# LipStick.net
KiCad netlist of a schematic drawn in EAGLE
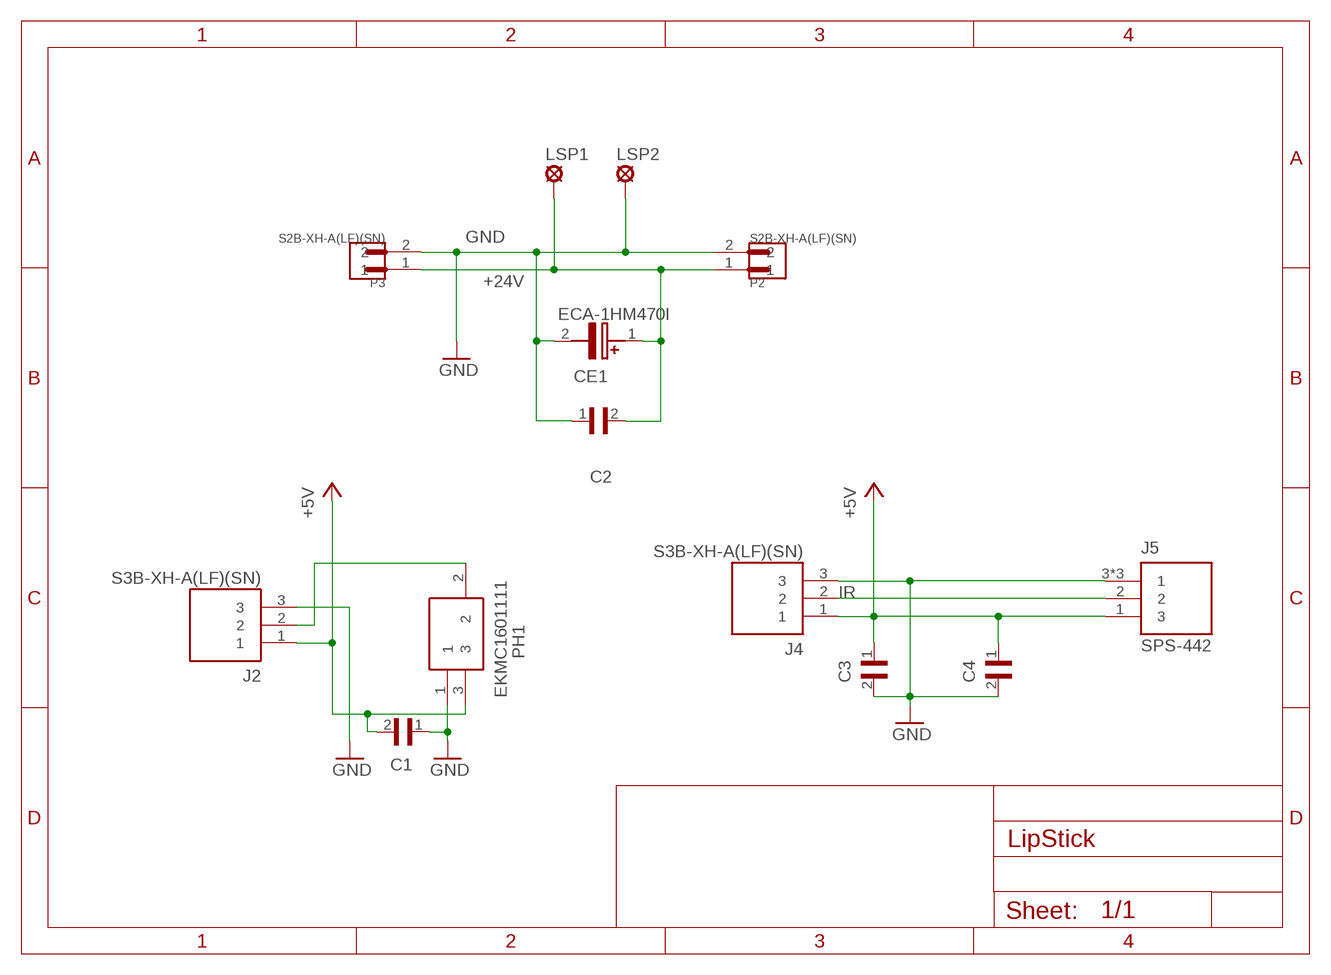
[diagram p0: schematic, sheet 1]

(export (version "E")
  (design (tool "Eeschema 10.0.6"))
  (components
    (comp (ref "C1")
      (value "GRM188R71H104KA93D")
      (footprint "eagle-import:CAPC1608X90N")
      (fields (field (name "MF") "Murata"))
      (libsource (lib "eagle-import") (part "GRM188R71H104KA93D"))
    )
    (comp (ref "C2")
      (value "GRM188R71H104KA93D")
      (footprint "eagle-import:CAPC1608X90N")
      (fields (field (name "MF") "Murata"))
      (libsource (lib "eagle-import") (part "GRM188R71H104KA93D"))
    )
    (comp (ref "C3")
      (value "GRM188R71H104KA93D")
      (footprint "eagle-import:CAPC1608X90N")
      (fields (field (name "MF") "Murata"))
      (libsource (lib "eagle-import") (part "GRM188R71H104KA93D"))
    )
    (comp (ref "C4")
      (value "GRM188R71H104KA93D")
      (footprint "eagle-import:CAPC1608X90N")
      (fields (field (name "MF") "Murata"))
      (libsource (lib "eagle-import") (part "GRM188R71H104KA93D"))
    )
    (comp (ref "CE1")
      (value "ECA-1HM470I")
      (footprint "eagle-import:CAPPRD250W55D630H1220")
      (fields (field (name "MOUSER_PART_NUMBER") "667-ECA-1HM470I"))
      (libsource (lib "eagle-import") (part "ECA-1HM470I"))
    )
    (comp (ref "J2")
      (value "S3B-XH-A(LF)(SN)")
      (footprint "eagle-import:JST_S3B-XH-A(LF)(SN)")
      (fields (field (name "DIGI-KEY_PART_NUMBER") "455-2250-ND") (field (name "MF") "JST Sales"))
      (libsource (lib "eagle-import") (part "S3B-XH-A(LF)(SN)"))
    )
    (comp (ref "J4")
      (value "S3B-XH-A(LF)(SN)")
      (footprint "eagle-import:JST_S3B-XH-A(LF)(SN)")
      (fields (field (name "DIGI-KEY_PART_NUMBER") "455-2250-ND") (field (name "MF") "JST Sales"))
      (libsource (lib "eagle-import") (part "S3B-XH-A(LF)(SN)"))
    )
    (comp (ref "J5")
      (value "SPS-442")
      (footprint "eagle-import:SPS-442")
      (fields
        (field (name "DIGI-KEY_PART_NUMBER") "455-2250-ND")
        (field (name "MF") "JST Sales")
        (field (name "MP") "S3B-XH-A(LF)(SN)")
      )
      (libsource (lib "eagle-import") (part "SPS-442"))
    )
    (comp (ref "LSP1")
      (value "SE14")
      (footprint "eagle-import:SE14")
      (libsource (lib "eagle-import") (part "SE14"))
    )
    (comp (ref "LSP2")
      (value "SE14")
      (footprint "eagle-import:SE14")
      (libsource (lib "eagle-import") (part "SE14"))
    )
    (comp (ref "P2")
      (value "S2B-XH-A(LF)(SN)")
      (footprint "eagle-import:JST_S2B-XH-A(LF)(SN)")
      (fields (field (name "MF") "JST Sales"))
      (libsource (lib "eagle-import") (part "S2B-XH-A(LF)(SN)"))
    )
    (comp (ref "P3")
      (value "S2B-XH-A(LF)(SN)")
      (footprint "eagle-import:JST_S2B-XH-A(LF)(SN)")
      (fields (field (name "MF") "JST Sales"))
      (libsource (lib "eagle-import") (part "S2B-XH-A(LF)(SN)"))
    )
    (comp (ref "PH1")
      (value "EKMC1601111")
      (footprint "eagle-import:VZ-STANDARD")
      (fields (field (name "MOUSER_PART_NUMBER") "769-EKMC1601111"))
      (libsource (lib "eagle-import") (part "EKMC1601111"))
    )
  )
  (nets
    (net (code "1") (name "+5V") (class "Default")
      (node (ref "C1") (pin "2") (pinfunction "2_2") (pintype "passive"))
      (node (ref "C3") (pin "1") (pinfunction "1_1") (pintype "passive"))
      (node (ref "C4") (pin "1") (pinfunction "1_1") (pintype "passive"))
      (node (ref "J2") (pin "1") (pinfunction "1_1") (pintype "passive"))
      (node (ref "J4") (pin "1") (pinfunction "1_1") (pintype "passive"))
      (node (ref "J5") (pin "1") (pinfunction "3_1") (pintype "passive"))
      (node (ref "PH1") (pin "3") (pinfunction "3_3") (pintype "bidirectional"))
    )
    (net (code "2") (name "/+24V") (class "Default")
      (node (ref "C2") (pin "2") (pinfunction "2_2") (pintype "passive"))
      (node (ref "CE1") (pin "1") (pinfunction "+_1") (pintype "bidirectional"))
      (node (ref "LSP1") (pin "MP") (pinfunction "MP_MP") (pintype "passive"))
      (node (ref "P2") (pin "1") (pinfunction "1_1") (pintype "passive"))
      (node (ref "P3") (pin "1") (pinfunction "1_1") (pintype "passive"))
    )
    (net (code "3") (name "/IR") (class "Default")
      (node (ref "J4") (pin "2") (pinfunction "2_2") (pintype "passive"))
      (node (ref "J5") (pin "2") (pinfunction "2_2") (pintype "passive"))
    )
    (net (code "4") (name "GND") (class "Default")
      (node (ref "C1") (pin "1") (pinfunction "1_1") (pintype "passive"))
      (node (ref "C2") (pin "1") (pinfunction "1_1") (pintype "passive"))
      (node (ref "C3") (pin "2") (pinfunction "2_2") (pintype "passive"))
      (node (ref "C4") (pin "2") (pinfunction "2_2") (pintype "passive"))
      (node (ref "CE1") (pin "2") (pinfunction "-_2") (pintype "bidirectional"))
      (node (ref "J2") (pin "3") (pinfunction "3_3") (pintype "passive"))
      (node (ref "J4") (pin "3") (pinfunction "3_3") (pintype "passive"))
      (node (ref "J5") (pin "3") (pinfunction "1_3") (pintype "passive"))
      (node (ref "J5") (pin "4") (pinfunction "1_4") (pintype "passive"))
      (node (ref "J5") (pin "5") (pinfunction "1_5") (pintype "passive"))
      (node (ref "LSP2") (pin "MP") (pinfunction "MP_MP") (pintype "passive"))
      (node (ref "P2") (pin "2") (pinfunction "2_2") (pintype "passive"))
      (node (ref "P3") (pin "2") (pinfunction "2_2") (pintype "passive"))
      (node (ref "PH1") (pin "1") (pinfunction "1_1") (pintype "bidirectional"))
    )
    (net (code "5") (name "Net-(J2-Pad2)") (class "Default")
      (node (ref "J2") (pin "2") (pinfunction "2_2") (pintype "passive"))
      (node (ref "PH1") (pin "2") (pinfunction "2_2") (pintype "bidirectional"))
    )
  )
)
